# PowerSupply.net
KiCad netlist of a schematic drawn in Altium Designer
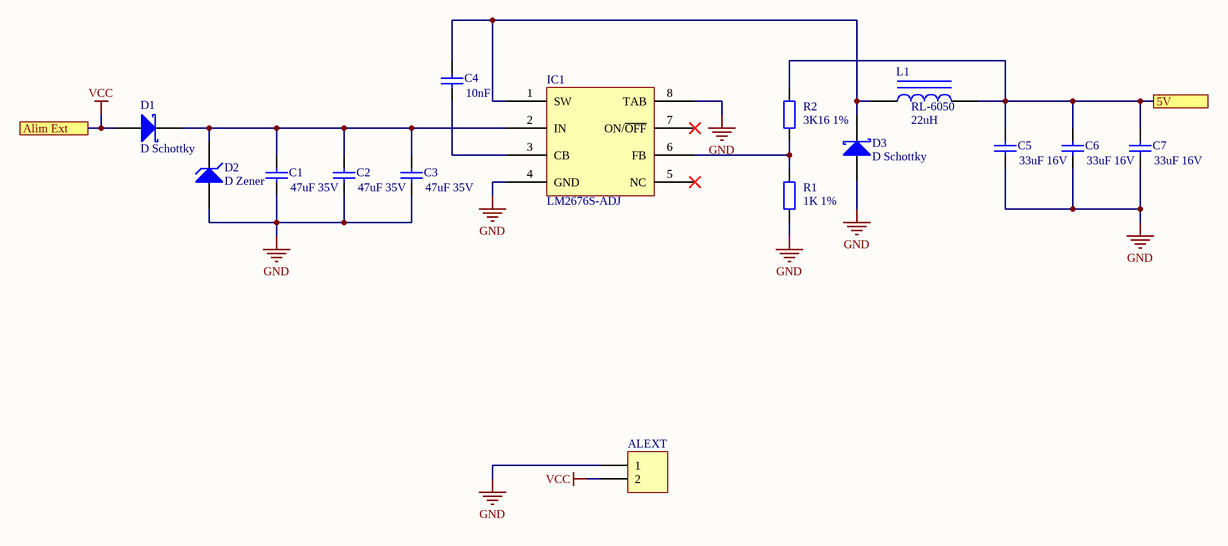
[diagram p0: PowerSupply.SchDoc]

(export (version "E")
  (design (tool "Eeschema 10.0.6"))
  (components
    (comp (ref "ALEXT")
      (value "Header 2")
      (footprint "CONN HEADER VERT 2POS 3.96MM")
      (description "Header, 2-Pin")
      (fields (field (name "PUBLISHER") "Altium Limited"))
      (libsource (lib "Miscellaneous Connectors") (part "Header 2"))
    )
    (comp (ref "C1")
      (value "47uF 35V")
      (footprint "KEMET Case D")
      (description "Capacitor")
      (fields
        (field (name "LCSC PART #") "C110229")
        (field (name "Comment") "Cap")
        (field (name "PUBLISHER") "Altium Limited")
      )
      (libsource (lib "Miscellaneous Devices") (part "Cap"))
    )
    (comp (ref "C2")
      (value "47uF 35V")
      (footprint "KEMET Case D")
      (description "Capacitor")
      (fields
        (field (name "LCSC PART #") "C110229")
        (field (name "Comment") "Cap")
        (field (name "PUBLISHER") "Altium Limited")
      )
      (libsource (lib "Miscellaneous Devices") (part "Cap"))
    )
    (comp (ref "C3")
      (value "47uF 35V")
      (footprint "KEMET Case D")
      (description "Capacitor")
      (fields
        (field (name "LCSC PART #") "C110229")
        (field (name "Comment") "Cap")
        (field (name "PUBLISHER") "Altium Limited")
      )
      (libsource (lib "Miscellaneous Devices") (part "Cap"))
    )
    (comp (ref "C4")
      (value "10nF")
      (footprint "RES0805")
      (description "Capacitor")
      (fields
        (field (name "LCSC PART #") "C1710")
        (field (name "Comment") "Cap")
        (field (name "PUBLISHER") "Altium Limited")
      )
      (libsource (lib "Miscellaneous Devices") (part "Cap"))
    )
    (comp (ref "C5")
      (value "33uF 16V")
      (footprint "RES 1206")
      (description "Capacitor")
      (fields (field (name "Comment") "Cap") (field (name "PUBLISHER") "Altium Limited"))
      (libsource (lib "Miscellaneous Devices") (part "Cap"))
    )
    (comp (ref "C6")
      (value "33uF 16V")
      (footprint "RES 1206")
      (description "Capacitor")
      (fields (field (name "Comment") "Cap") (field (name "PUBLISHER") "Altium Limited"))
      (libsource (lib "Miscellaneous Devices") (part "Cap"))
    )
    (comp (ref "C7")
      (value "33uF 16V")
      (footprint "RES 1206")
      (description "Capacitor")
      (fields (field (name "Comment") "Cap") (field (name "PUBLISHER") "Altium Limited"))
      (libsource (lib "Miscellaneous Devices") (part "Cap"))
    )
    (comp (ref "D1")
      (value "D Schottky")
      (footprint "SMB")
      (description "B340B-13-F")
      (fields (field (name "LCSC PART #") "C85099") (field (name "PUBLISHER") "Altium Limited"))
      (libsource (lib "Miscellaneous Devices") (part "D Schottky"))
    )
    (comp (ref "D2")
      (value "D Zener")
      (footprint "SMB")
      (description "SMBJ24A")
      (fields (field (name "LCSC PART #") "C3018876") (field (name "PUBLISHER") "Altium Limited"))
      (libsource (lib "Miscellaneous Devices") (part "D Zener"))
    )
    (comp (ref "D3")
      (value "D Schottky")
      (footprint "SMB")
      (description "B340B-13-F")
      (fields (field (name "LCSC PART #") "C85099") (field (name "PUBLISHER") "Altium Limited"))
      (libsource (lib "Miscellaneous Devices") (part "D Schottky"))
    )
    (comp (ref "IC1")
      (value "LM2676S-ADJ")
      (footprint "DPAK127P1435X464-8N")
      (libsource (lib "LM2676S-ADJ") (part "LM2676S-ADJ"))
    )
    (comp (ref "L1")
      (value "RL-6050")
      (footprint "RL-6050")
      (description "Magnetic-Core Inductor")
      (fields (field (name "ALTIUM_VALUE") "22uH") (field (name "PUBLISHER") "Altium Limited"))
      (libsource (lib "Miscellaneous Devices") (part "Inductor Iron"))
    )
    (comp (ref "R1")
      (value "1K 1%")
      (footprint "RES0805")
      (description "Resistor")
      (fields
        (field (name "LCSC PART #") "C416040")
        (field (name "Comment") "Res2")
        (field (name "PUBLISHER") "Altium Limited")
      )
      (libsource (lib "Miscellaneous Devices") (part "Res2"))
    )
    (comp (ref "R2")
      (value "3K16 1%")
      (footprint "RES0805")
      (description "Resistor")
      (fields
        (field (name "LCSC PART #") "C170878")
        (field (name "Comment") "Res2")
        (field (name "PUBLISHER") "Altium Limited")
      )
      (libsource (lib "Miscellaneous Devices") (part "Res2"))
    )
  )
  (nets
    (net (code "1") (name "/5V") (class "Default")
      (node (ref "C5") (pin "2") (pinfunction "2_2") (pintype "passive"))
      (node (ref "C6") (pin "2") (pinfunction "2_2") (pintype "passive"))
      (node (ref "C7") (pin "2") (pinfunction "2_2") (pintype "passive"))
      (node (ref "L1") (pin "2") (pinfunction "2_2") (pintype "passive"))
      (node (ref "R2") (pin "2") (pinfunction "2_2") (pintype "passive"))
    )
    (net (code "2") (name "GND") (class "Default")
      (node (ref "ALEXT") (pin "1") (pinfunction "1_1") (pintype "passive"))
      (node (ref "C1") (pin "2") (pinfunction "2_2") (pintype "passive"))
      (node (ref "C2") (pin "2") (pinfunction "2_2") (pintype "passive"))
      (node (ref "C3") (pin "2") (pinfunction "2_2") (pintype "passive"))
      (node (ref "C5") (pin "1") (pinfunction "1_1") (pintype "passive"))
      (node (ref "C6") (pin "1") (pinfunction "1_1") (pintype "passive"))
      (node (ref "C7") (pin "1") (pinfunction "1_1") (pintype "passive"))
      (node (ref "D2") (pin "1") (pinfunction "A_1") (pintype "passive"))
      (node (ref "D3") (pin "1") (pinfunction "A_1") (pintype "passive"))
      (node (ref "IC1") (pin "4") (pinfunction "GND_4") (pintype "passive"))
      (node (ref "IC1") (pin "8") (pinfunction "TAB_8") (pintype "passive"))
      (node (ref "R1") (pin "1") (pinfunction "1_1") (pintype "passive"))
    )
    (net (code "3") (name "Net-(D1-K)") (class "Default")
      (node (ref "C1") (pin "1") (pinfunction "1_1") (pintype "passive"))
      (node (ref "C2") (pin "1") (pinfunction "1_1") (pintype "passive"))
      (node (ref "C3") (pin "1") (pinfunction "1_1") (pintype "passive"))
      (node (ref "D1") (pin "2") (pinfunction "K_2") (pintype "passive"))
      (node (ref "D2") (pin "2") (pinfunction "K_2") (pintype "passive"))
      (node (ref "IC1") (pin "2") (pinfunction "IN_2") (pintype "passive"))
    )
    (net (code "4") (name "Net-(D3-K)") (class "Default")
      (node (ref "C4") (pin "2") (pinfunction "2_2") (pintype "passive"))
      (node (ref "D3") (pin "2") (pinfunction "K_2") (pintype "passive"))
      (node (ref "IC1") (pin "1") (pinfunction "SW_1") (pintype "passive"))
      (node (ref "L1") (pin "1") (pinfunction "1_1") (pintype "passive"))
    )
    (net (code "5") (name "Net-(IC1-CB)") (class "Default")
      (node (ref "C4") (pin "1") (pinfunction "1_1") (pintype "passive"))
      (node (ref "IC1") (pin "3") (pinfunction "CB_3") (pintype "passive"))
    )
    (net (code "6") (name "Net-(IC1-FB)") (class "Default")
      (node (ref "IC1") (pin "6") (pinfunction "FB_6") (pintype "passive"))
      (node (ref "R1") (pin "2") (pinfunction "2_2") (pintype "passive"))
      (node (ref "R2") (pin "1") (pinfunction "1_1") (pintype "passive"))
    )
    (net (code "7") (name "VCC") (class "Default")
      (node (ref "ALEXT") (pin "2") (pinfunction "2_2") (pintype "passive"))
      (node (ref "D1") (pin "1") (pinfunction "A_1") (pintype "passive"))
    )
    (net (code "8") (name "unconnected-(IC1-NC-Pad5)") (class "Default")
      (node (ref "IC1") (pin "5") (pinfunction "NC_5") (pintype "passive+no_connect"))
    )
    (net (code "9") (name "unconnected-(IC1-ON{slash}~{OFF}-Pad7)") (class "Default")
      (node (ref "IC1") (pin "7") (pinfunction "ON/~{OFF}_7") (pintype "passive+no_connect"))
    )
  )
)
